# SNES1Chip_SCIC_IGR_D4_Takt_SMD.net
KiCad netlist of a schematic drawn in EAGLE
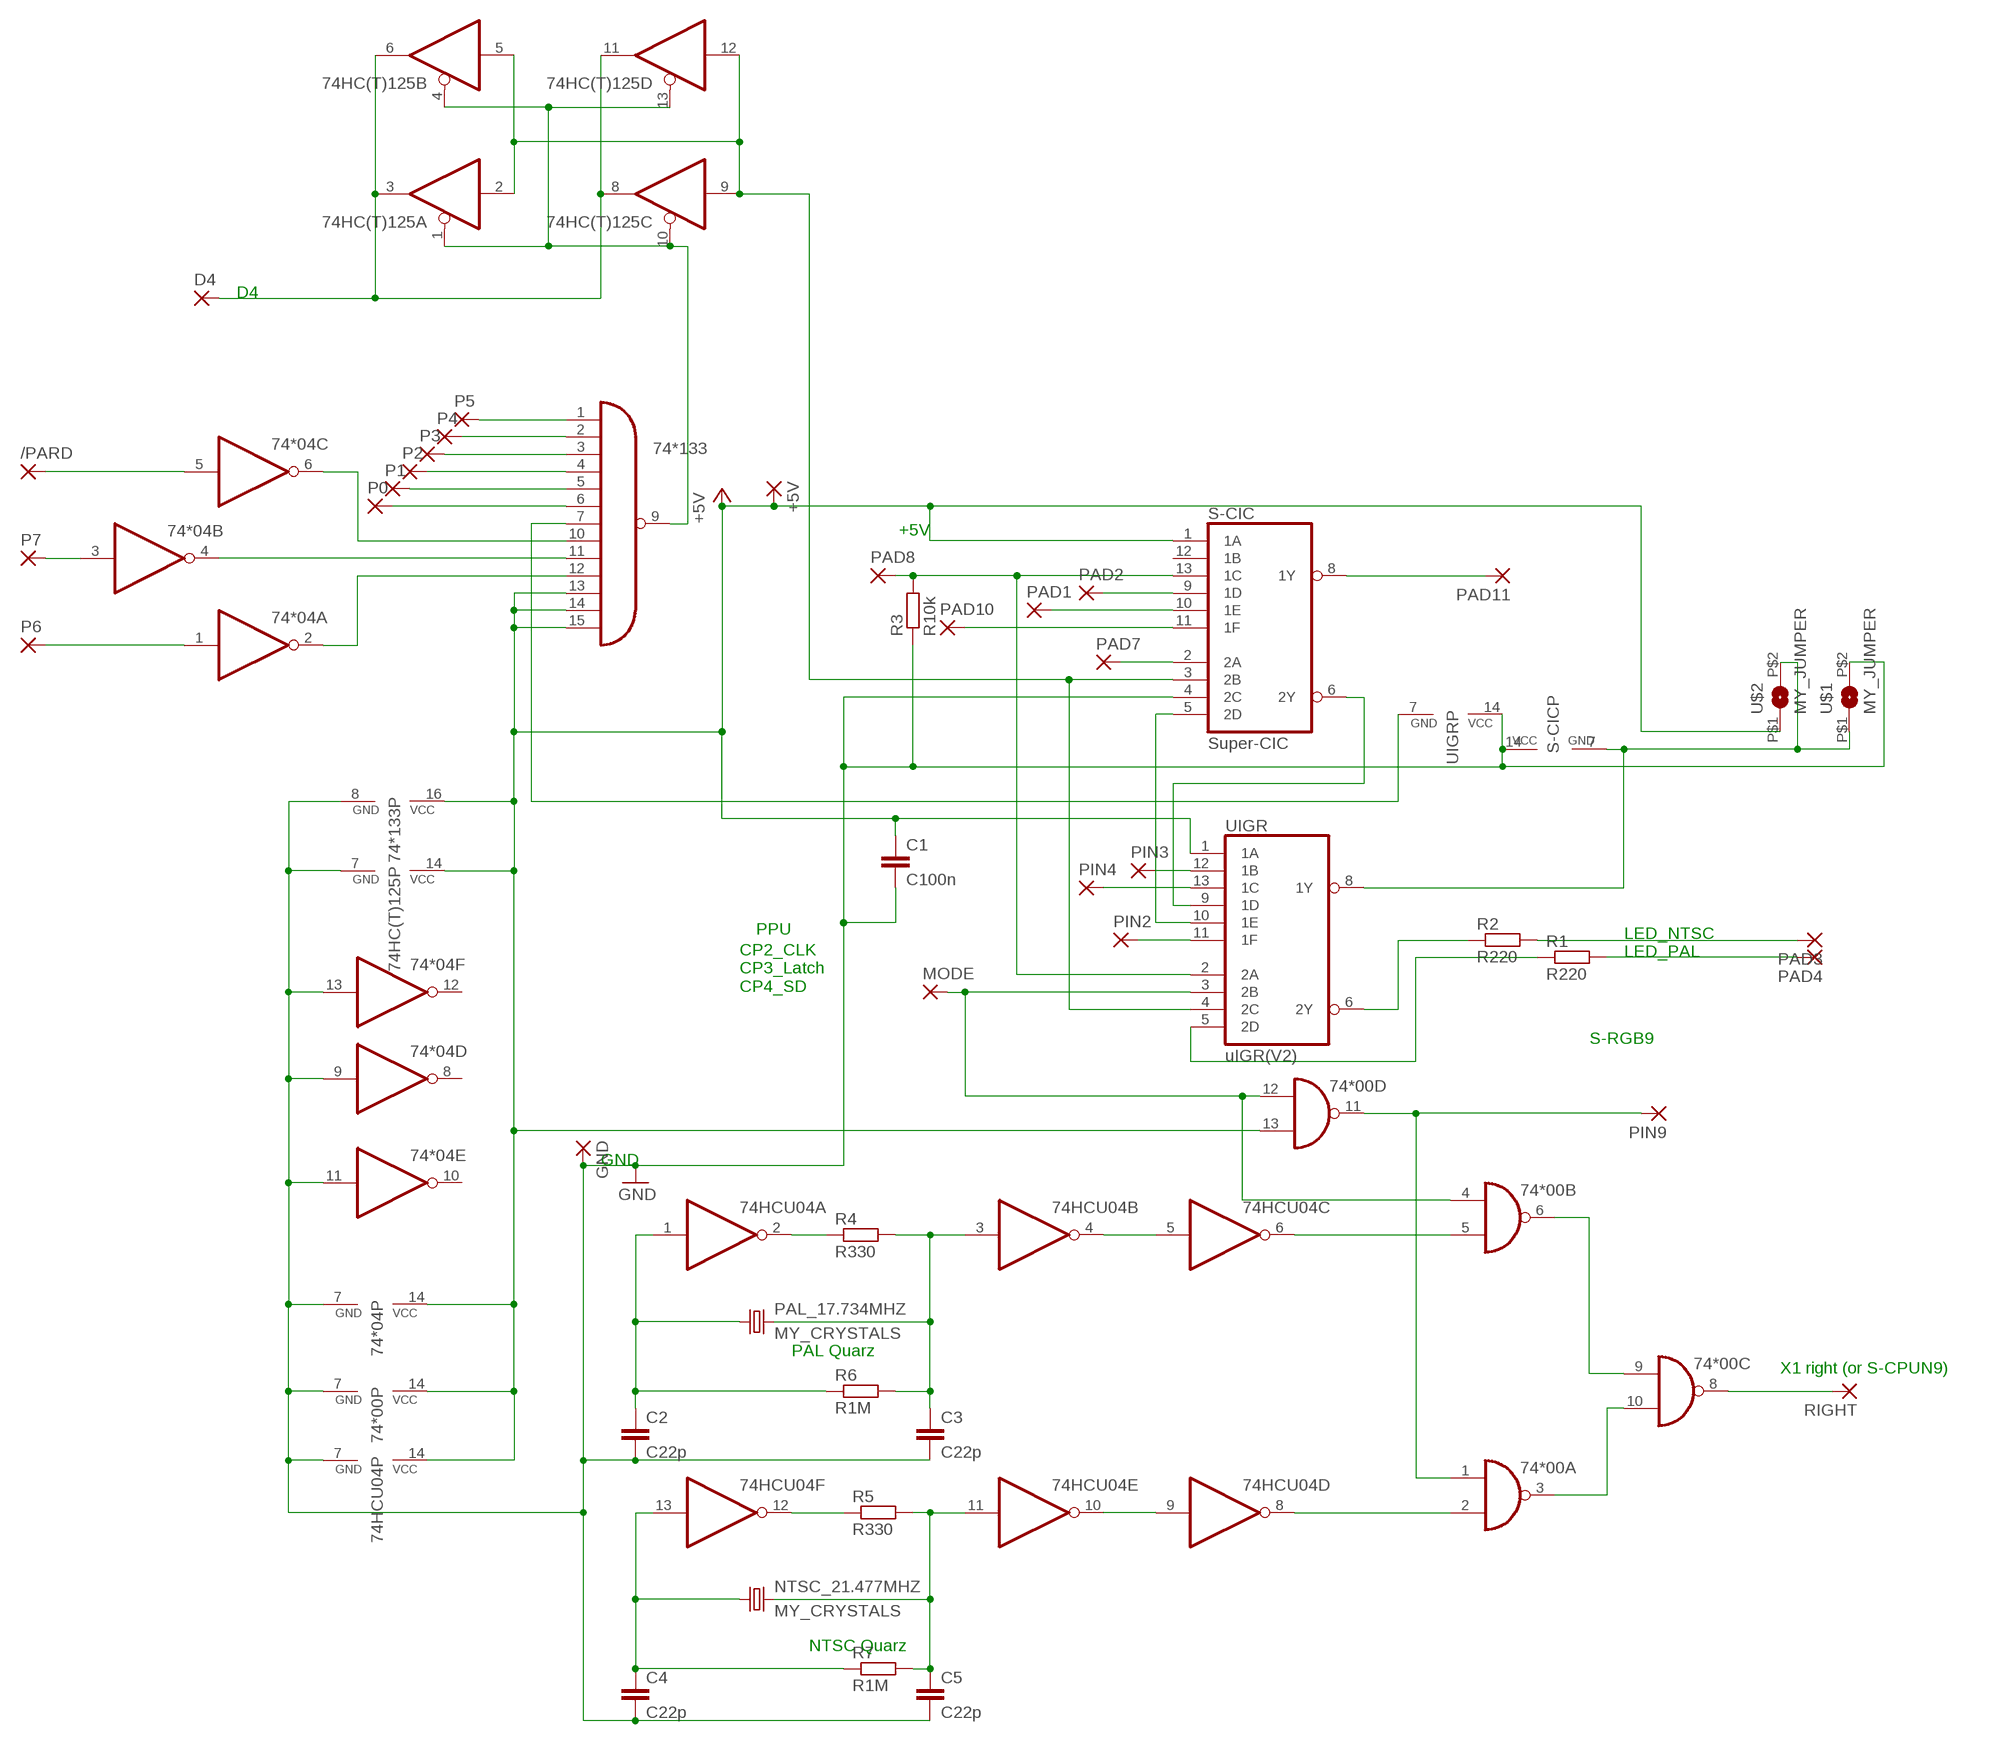
[diagram p0: schematic, sheet 1]

(export (version "E")
  (design (tool "Eeschema 10.0.6"))
  (components
    (comp (ref "+5V")
      (value "SMD2")
      (footprint "eagle-import:SMD1,27-2,54")
      (libsource (lib "eagle-import") (part "SMD2"))
    )
    (comp (ref "/PARD")
      (value "SMD2")
      (footprint "eagle-import:SMD1,27-2,54")
      (libsource (lib "eagle-import") (part "SMD2"))
    )
    (comp (ref "74*00")
      (value "7400D")
      (footprint "eagle-import:SO14")
      (libsource (lib "eagle-import") (part "7400D"))
    )
    (comp (ref "74*04")
      (value "74S04D")
      (footprint "eagle-import:SO14")
      (libsource (lib "eagle-import") (part "7404DS"))
    )
    (comp (ref "74*133")
      (value "74S133D")
      (footprint "eagle-import:SO16")
      (libsource (lib "eagle-import") (part "74133DS"))
    )
    (comp (ref "74HC(T)125")
      (value "74HCT125D")
      (footprint "eagle-import:SO14")
      (libsource (lib "eagle-import") (part "74125DHCT"))
    )
    (comp (ref "74HCU04")
      (value "74HC04D")
      (footprint "eagle-import:SO14")
      (libsource (lib "eagle-import") (part "7404DHC"))
    )
    (comp (ref "C1")
      (value "C100n")
      (footprint "eagle-import:C0805")
      (libsource (lib "eagle-import") (part "C-EUC0805"))
    )
    (comp (ref "C2")
      (value "C22p")
      (footprint "eagle-import:C0805")
      (libsource (lib "eagle-import") (part "C-EUC0805"))
    )
    (comp (ref "C3")
      (value "C22p")
      (footprint "eagle-import:C0805")
      (libsource (lib "eagle-import") (part "C-EUC0805"))
    )
    (comp (ref "C4")
      (value "C22p")
      (footprint "eagle-import:C0805")
      (libsource (lib "eagle-import") (part "C-EUC0805"))
    )
    (comp (ref "C5")
      (value "C22p")
      (footprint "eagle-import:C0805")
      (libsource (lib "eagle-import") (part "C-EUC0805"))
    )
    (comp (ref "D4")
      (value "SMD2")
      (footprint "eagle-import:SMD1,27-2,54")
      (libsource (lib "eagle-import") (part "SMD2"))
    )
    (comp (ref "GND")
      (value "SMD2")
      (footprint "eagle-import:SMD1,27-2,54")
      (libsource (lib "eagle-import") (part "SMD2"))
    )
    (comp (ref "MODE")
      (value "SMD2")
      (footprint "eagle-import:SMD1,27-2,54")
      (libsource (lib "eagle-import") (part "SMD2"))
    )
    (comp (ref "NTSC_21.477MHZ")
      (value "MY_CRYSTALS")
      (footprint "eagle-import:MY_SMD_CRYSTAL2")
      (libsource (lib "eagle-import") (part "MY_CRYSTALS"))
    )
    (comp (ref "P0")
      (value "SMD2")
      (footprint "eagle-import:SMD1,27-2,54")
      (libsource (lib "eagle-import") (part "SMD2"))
    )
    (comp (ref "P1")
      (value "SMD2")
      (footprint "eagle-import:SMD1,27-2,54")
      (libsource (lib "eagle-import") (part "SMD2"))
    )
    (comp (ref "P2")
      (value "SMD2")
      (footprint "eagle-import:SMD1,27-2,54")
      (libsource (lib "eagle-import") (part "SMD2"))
    )
    (comp (ref "P3")
      (value "SMD2")
      (footprint "eagle-import:SMD1,27-2,54")
      (libsource (lib "eagle-import") (part "SMD2"))
    )
    (comp (ref "P4")
      (value "SMD2")
      (footprint "eagle-import:SMD1,27-2,54")
      (libsource (lib "eagle-import") (part "SMD2"))
    )
    (comp (ref "P5")
      (value "SMD2")
      (footprint "eagle-import:SMD1,27-2,54")
      (libsource (lib "eagle-import") (part "SMD2"))
    )
    (comp (ref "P6")
      (value "SMD2")
      (footprint "eagle-import:SMD1,27-2,54")
      (libsource (lib "eagle-import") (part "SMD2"))
    )
    (comp (ref "P7")
      (value "SMD2")
      (footprint "eagle-import:SMD1,27-2,54")
      (libsource (lib "eagle-import") (part "SMD2"))
    )
    (comp (ref "PAD1")
      (value "SMD2")
      (footprint "eagle-import:SMD1,27-2,54")
      (libsource (lib "eagle-import") (part "SMD2"))
    )
    (comp (ref "PAD2")
      (value "SMD2")
      (footprint "eagle-import:SMD1,27-2,54")
      (libsource (lib "eagle-import") (part "SMD2"))
    )
    (comp (ref "PAD3")
      (value "SMD2")
      (footprint "eagle-import:SMD1,27-2,54")
      (libsource (lib "eagle-import") (part "SMD2"))
    )
    (comp (ref "PAD4")
      (value "SMD2")
      (footprint "eagle-import:SMD1,27-2,54")
      (libsource (lib "eagle-import") (part "SMD2"))
    )
    (comp (ref "PAD7")
      (value "SMD2")
      (footprint "eagle-import:SMD1,27-2,54")
      (libsource (lib "eagle-import") (part "SMD2"))
    )
    (comp (ref "PAD8")
      (value "SMD2")
      (footprint "eagle-import:SMD1,27-2,54")
      (libsource (lib "eagle-import") (part "SMD2"))
    )
    (comp (ref "PAD10")
      (value "SMD2")
      (footprint "eagle-import:SMD1,27-2,54")
      (libsource (lib "eagle-import") (part "SMD2"))
    )
    (comp (ref "PAD11")
      (value "SMD2")
      (footprint "eagle-import:SMD1,27-2,54")
      (libsource (lib "eagle-import") (part "SMD2"))
    )
    (comp (ref "PAL_17.734MHZ")
      (value "MY_CRYSTALS")
      (footprint "eagle-import:MY_SMD_CRYSTAL2")
      (libsource (lib "eagle-import") (part "MY_CRYSTALS"))
    )
    (comp (ref "PIN2")
      (value "SMD2")
      (footprint "eagle-import:SMD1,27-2,54")
      (libsource (lib "eagle-import") (part "SMD2"))
    )
    (comp (ref "PIN3")
      (value "SMD2")
      (footprint "eagle-import:SMD1,27-2,54")
      (libsource (lib "eagle-import") (part "SMD2"))
    )
    (comp (ref "PIN4")
      (value "SMD2")
      (footprint "eagle-import:SMD1,27-2,54")
      (libsource (lib "eagle-import") (part "SMD2"))
    )
    (comp (ref "PIN9")
      (value "SMD2")
      (footprint "eagle-import:SMD1,27-2,54")
      (libsource (lib "eagle-import") (part "SMD2"))
    )
    (comp (ref "R1")
      (value "R220")
      (footprint "eagle-import:R0805")
      (libsource (lib "eagle-import") (part "R-EU_R0805"))
    )
    (comp (ref "R2")
      (value "R220")
      (footprint "eagle-import:R0805")
      (libsource (lib "eagle-import") (part "R-EU_R0805"))
    )
    (comp (ref "R3")
      (value "R10k")
      (footprint "eagle-import:R0805")
      (libsource (lib "eagle-import") (part "R-EU_R0805"))
    )
    (comp (ref "R4")
      (value "R330")
      (footprint "eagle-import:R0805")
      (libsource (lib "eagle-import") (part "R-EU_R0805"))
    )
    (comp (ref "R5")
      (value "R330")
      (footprint "eagle-import:R0805")
      (libsource (lib "eagle-import") (part "R-EU_R0805"))
    )
    (comp (ref "R6")
      (value "R1M")
      (footprint "eagle-import:R0805")
      (libsource (lib "eagle-import") (part "R-EU_R0805"))
    )
    (comp (ref "R7")
      (value "R1M")
      (footprint "eagle-import:R0805")
      (libsource (lib "eagle-import") (part "R-EU_R0805"))
    )
    (comp (ref "RIGHT")
      (value "SMD2")
      (footprint "eagle-import:SMD1,27-2,54")
      (libsource (lib "eagle-import") (part "SMD2"))
    )
    (comp (ref "S-CIC")
      (value "Super-CIC")
      (footprint "eagle-import:SO14")
      (libsource (lib "eagle-import") (part "7451DHC"))
    )
    (comp (ref "U$1")
      (value "MY_JUMPER")
      (footprint "eagle-import:MYJUMP")
      (libsource (lib "eagle-import") (part "MY_JUMPER"))
    )
    (comp (ref "U$2")
      (value "MY_JUMPER")
      (footprint "eagle-import:MYJUMP")
      (libsource (lib "eagle-import") (part "MY_JUMPER"))
    )
    (comp (ref "UIGR")
      (value "uIGR(V2)")
      (footprint "eagle-import:SO14")
      (libsource (lib "eagle-import") (part "7451DHC"))
    )
  )
  (nets
    (net (code "1") (name "+5V") (class "Default")
      (node (ref "+5V") (pin "1") (pinfunction "P_1") (pintype "passive"))
      (node (ref "74*00") (pin "13") (pinfunction "I1_13") (pintype "input"))
      (node (ref "74*00") (pin "14") (pinfunction "VCC_14") (pintype "power_in"))
      (node (ref "74*04") (pin "14") (pinfunction "VCC_14") (pintype "power_in"))
      (node (ref "74*133") (pin "13") (pinfunction "I10_13") (pintype "input"))
      (node (ref "74*133") (pin "14") (pinfunction "I11_14") (pintype "input"))
      (node (ref "74*133") (pin "15") (pinfunction "I12_15") (pintype "input"))
      (node (ref "74*133") (pin "16") (pinfunction "VCC_16") (pintype "power_in"))
      (node (ref "74HC(T)125") (pin "14") (pinfunction "VCC_14") (pintype "power_in"))
      (node (ref "74HCU04") (pin "14") (pinfunction "VCC_14") (pintype "power_in"))
      (node (ref "C1") (pin "1") (pinfunction "1_1") (pintype "passive"))
      (node (ref "S-CIC") (pin "1") (pinfunction "1A_1") (pintype "input"))
      (node (ref "U$2") (pin "P$1") (pinfunction "1_P$1") (pintype "passive"))
      (node (ref "UIGR") (pin "1") (pinfunction "1A_1") (pintype "input"))
    )
    (net (code "2") (name "GND") (class "Default")
      (node (ref "74*00") (pin "7") (pinfunction "GND_7") (pintype "power_in"))
      (node (ref "74*04") (pin "11") (pinfunction "I_11") (pintype "input"))
      (node (ref "74*04") (pin "13") (pinfunction "I_13") (pintype "input"))
      (node (ref "74*04") (pin "7") (pinfunction "GND_7") (pintype "power_in"))
      (node (ref "74*04") (pin "9") (pinfunction "I_9") (pintype "input"))
      (node (ref "74*133") (pin "8") (pinfunction "GND_8") (pintype "power_in"))
      (node (ref "74HC(T)125") (pin "7") (pinfunction "GND_7") (pintype "power_in"))
      (node (ref "74HCU04") (pin "7") (pinfunction "GND_7") (pintype "power_in"))
      (node (ref "C1") (pin "2") (pinfunction "2_2") (pintype "passive"))
      (node (ref "C2") (pin "2") (pinfunction "2_2") (pintype "passive"))
      (node (ref "C3") (pin "2") (pinfunction "2_2") (pintype "passive"))
      (node (ref "C4") (pin "2") (pinfunction "2_2") (pintype "passive"))
      (node (ref "C5") (pin "2") (pinfunction "2_2") (pintype "passive"))
      (node (ref "GND") (pin "1") (pinfunction "P_1") (pintype "passive"))
      (node (ref "R3") (pin "1") (pinfunction "1_1") (pintype "passive"))
      (node (ref "S-CIC") (pin "14") (pinfunction "VCC_14") (pintype "power_in"))
      (node (ref "S-CIC") (pin "4") (pinfunction "2C_4") (pintype "input"))
      (node (ref "U$1") (pin "P$2") (pinfunction "2_P$2") (pintype "passive"))
      (node (ref "UIGR") (pin "14") (pinfunction "VCC_14") (pintype "power_in"))
    )
    (net (code "3") (name "Net-(/PARD-P)") (class "Default")
      (node (ref "/PARD") (pin "1") (pinfunction "P_1") (pintype "passive"))
      (node (ref "74*04") (pin "5") (pinfunction "I_5") (pintype "input"))
    )
    (net (code "4") (name "Net-(74*00A-I0)") (class "Default")
      (node (ref "74*00") (pin "1") (pinfunction "I0_1") (pintype "input"))
      (node (ref "74*00") (pin "11") (pinfunction "O_11") (pintype "output"))
      (node (ref "PIN9") (pin "1") (pinfunction "P_1") (pintype "passive"))
    )
    (net (code "5") (name "Net-(74*00A-I1)") (class "Default")
      (node (ref "74*00") (pin "2") (pinfunction "I1_2") (pintype "input"))
      (node (ref "74HCU04") (pin "8") (pinfunction "O_8") (pintype "output"))
    )
    (net (code "6") (name "Net-(74*00A-O)") (class "Default")
      (node (ref "74*00") (pin "10") (pinfunction "I1_10") (pintype "input"))
      (node (ref "74*00") (pin "3") (pinfunction "O_3") (pintype "output"))
    )
    (net (code "7") (name "Net-(74*00B-I0)") (class "Default")
      (node (ref "74*00") (pin "12") (pinfunction "I0_12") (pintype "input"))
      (node (ref "74*00") (pin "4") (pinfunction "I0_4") (pintype "input"))
      (node (ref "MODE") (pin "1") (pinfunction "P_1") (pintype "passive"))
      (node (ref "UIGR") (pin "3") (pinfunction "2B_3") (pintype "input"))
    )
    (net (code "8") (name "Net-(74*00B-I1)") (class "Default")
      (node (ref "74*00") (pin "5") (pinfunction "I1_5") (pintype "input"))
      (node (ref "74HCU04") (pin "6") (pinfunction "O_6") (pintype "output"))
    )
    (net (code "9") (name "Net-(74*00B-O)") (class "Default")
      (node (ref "74*00") (pin "6") (pinfunction "O_6") (pintype "output"))
      (node (ref "74*00") (pin "9") (pinfunction "I0_9") (pintype "input"))
    )
    (net (code "10") (name "Net-(74*00C-O)") (class "Default")
      (node (ref "74*00") (pin "8") (pinfunction "O_8") (pintype "output"))
      (node (ref "RIGHT") (pin "1") (pinfunction "P_1") (pintype "passive"))
    )
    (net (code "11") (name "Net-(74*04A-I)") (class "Default")
      (node (ref "74*04") (pin "1") (pinfunction "I_1") (pintype "input"))
      (node (ref "P6") (pin "1") (pinfunction "P_1") (pintype "passive"))
    )
    (net (code "12") (name "Net-(74*04A-O)") (class "Default")
      (node (ref "74*04") (pin "2") (pinfunction "O_2") (pintype "output"))
      (node (ref "74*133") (pin "12") (pinfunction "I9_12") (pintype "input"))
    )
    (net (code "13") (name "Net-(74*04B-I)") (class "Default")
      (node (ref "74*04") (pin "3") (pinfunction "I_3") (pintype "input"))
      (node (ref "P7") (pin "1") (pinfunction "P_1") (pintype "passive"))
    )
    (net (code "14") (name "Net-(74*04B-O)") (class "Default")
      (node (ref "74*04") (pin "4") (pinfunction "O_4") (pintype "output"))
      (node (ref "74*133") (pin "11") (pinfunction "I8_11") (pintype "input"))
    )
    (net (code "15") (name "Net-(74*04C-O)") (class "Default")
      (node (ref "74*04") (pin "6") (pinfunction "O_6") (pintype "output"))
      (node (ref "74*133") (pin "10") (pinfunction "I7_10") (pintype "input"))
    )
    (net (code "16") (name "Net-(74*133A-I0)") (class "Default")
      (node (ref "74*133") (pin "1") (pinfunction "I0_1") (pintype "input"))
      (node (ref "P5") (pin "1") (pinfunction "P_1") (pintype "passive"))
    )
    (net (code "17") (name "Net-(74*133A-I1)") (class "Default")
      (node (ref "74*133") (pin "2") (pinfunction "I1_2") (pintype "input"))
      (node (ref "P4") (pin "1") (pinfunction "P_1") (pintype "passive"))
    )
    (net (code "18") (name "Net-(74*133A-I2)") (class "Default")
      (node (ref "74*133") (pin "3") (pinfunction "I2_3") (pintype "input"))
      (node (ref "P3") (pin "1") (pinfunction "P_1") (pintype "passive"))
    )
    (net (code "19") (name "Net-(74*133A-I3)") (class "Default")
      (node (ref "74*133") (pin "4") (pinfunction "I3_4") (pintype "input"))
      (node (ref "P2") (pin "1") (pinfunction "P_1") (pintype "passive"))
    )
    (net (code "20") (name "Net-(74*133A-I4)") (class "Default")
      (node (ref "74*133") (pin "5") (pinfunction "I4_5") (pintype "input"))
      (node (ref "P1") (pin "1") (pinfunction "P_1") (pintype "passive"))
    )
    (net (code "21") (name "Net-(74*133A-I5)") (class "Default")
      (node (ref "74*133") (pin "6") (pinfunction "I5_6") (pintype "input"))
      (node (ref "P0") (pin "1") (pinfunction "P_1") (pintype "passive"))
    )
    (net (code "22") (name "Net-(74*133A-I6)") (class "Default")
      (node (ref "74*133") (pin "7") (pinfunction "I6_7") (pintype "input"))
      (node (ref "UIGR") (pin "7") (pinfunction "GND_7") (pintype "power_in"))
    )
    (net (code "23") (name "Net-(74*133A-O)") (class "Default")
      (node (ref "74*133") (pin "9") (pinfunction "O_9") (pintype "output"))
      (node (ref "74HC(T)125") (pin "1") (pinfunction "OE_1") (pintype "input"))
      (node (ref "74HC(T)125") (pin "10") (pinfunction "OE_10") (pintype "input"))
      (node (ref "74HC(T)125") (pin "13") (pinfunction "OE_13") (pintype "input"))
      (node (ref "74HC(T)125") (pin "4") (pinfunction "OE_4") (pintype "input"))
    )
    (net (code "24") (name "Net-(74HC(T)125A-I)") (class "Default")
      (node (ref "74HC(T)125") (pin "12") (pinfunction "I_12") (pintype "input"))
      (node (ref "74HC(T)125") (pin "2") (pinfunction "I_2") (pintype "input"))
      (node (ref "74HC(T)125") (pin "5") (pinfunction "I_5") (pintype "input"))
      (node (ref "74HC(T)125") (pin "9") (pinfunction "I_9") (pintype "input"))
      (node (ref "S-CIC") (pin "3") (pinfunction "2B_3") (pintype "input"))
      (node (ref "UIGR") (pin "4") (pinfunction "2C_4") (pintype "input"))
    )
    (net (code "25") (name "Net-(74HC(T)125A-O)") (class "Default")
      (node (ref "74HC(T)125") (pin "11") (pinfunction "O_11") (pintype "tri_state"))
      (node (ref "74HC(T)125") (pin "3") (pinfunction "O_3") (pintype "tri_state"))
      (node (ref "74HC(T)125") (pin "6") (pinfunction "O_6") (pintype "tri_state"))
      (node (ref "74HC(T)125") (pin "8") (pinfunction "O_8") (pintype "tri_state"))
      (node (ref "D4") (pin "1") (pinfunction "P_1") (pintype "passive"))
    )
    (net (code "26") (name "Net-(74HCU04A-I)") (class "Default")
      (node (ref "74HCU04") (pin "1") (pinfunction "I_1") (pintype "input"))
      (node (ref "C2") (pin "1") (pinfunction "1_1") (pintype "passive"))
      (node (ref "PAL_17.734MHZ") (pin "1") (pinfunction "1_1") (pintype "passive"))
      (node (ref "R6") (pin "1") (pinfunction "1_1") (pintype "passive"))
    )
    (net (code "27") (name "Net-(74HCU04A-O)") (class "Default")
      (node (ref "74HCU04") (pin "2") (pinfunction "O_2") (pintype "output"))
      (node (ref "R4") (pin "1") (pinfunction "1_1") (pintype "passive"))
    )
    (net (code "28") (name "Net-(74HCU04B-I)") (class "Default")
      (node (ref "74HCU04") (pin "3") (pinfunction "I_3") (pintype "input"))
      (node (ref "C3") (pin "1") (pinfunction "1_1") (pintype "passive"))
      (node (ref "PAL_17.734MHZ") (pin "2") (pinfunction "2_2") (pintype "passive"))
      (node (ref "R4") (pin "2") (pinfunction "2_2") (pintype "passive"))
      (node (ref "R6") (pin "2") (pinfunction "2_2") (pintype "passive"))
    )
    (net (code "29") (name "Net-(74HCU04B-O)") (class "Default")
      (node (ref "74HCU04") (pin "4") (pinfunction "O_4") (pintype "output"))
      (node (ref "74HCU04") (pin "5") (pinfunction "I_5") (pintype "input"))
    )
    (net (code "30") (name "Net-(74HCU04D-I)") (class "Default")
      (node (ref "74HCU04") (pin "10") (pinfunction "O_10") (pintype "output"))
      (node (ref "74HCU04") (pin "9") (pinfunction "I_9") (pintype "input"))
    )
    (net (code "31") (name "Net-(74HCU04E-I)") (class "Default")
      (node (ref "74HCU04") (pin "11") (pinfunction "I_11") (pintype "input"))
      (node (ref "C5") (pin "1") (pinfunction "1_1") (pintype "passive"))
      (node (ref "NTSC_21.477MHZ") (pin "2") (pinfunction "2_2") (pintype "passive"))
      (node (ref "R5") (pin "2") (pinfunction "2_2") (pintype "passive"))
      (node (ref "R7") (pin "2") (pinfunction "2_2") (pintype "passive"))
    )
    (net (code "32") (name "Net-(74HCU04F-I)") (class "Default")
      (node (ref "74HCU04") (pin "13") (pinfunction "I_13") (pintype "input"))
      (node (ref "C4") (pin "1") (pinfunction "1_1") (pintype "passive"))
      (node (ref "NTSC_21.477MHZ") (pin "1") (pinfunction "1_1") (pintype "passive"))
      (node (ref "R7") (pin "1") (pinfunction "1_1") (pintype "passive"))
    )
    (net (code "33") (name "Net-(74HCU04F-O)") (class "Default")
      (node (ref "74HCU04") (pin "12") (pinfunction "O_12") (pintype "output"))
      (node (ref "R5") (pin "1") (pinfunction "1_1") (pintype "passive"))
    )
    (net (code "34") (name "Net-(PAD1-P)") (class "Default")
      (node (ref "PAD1") (pin "1") (pinfunction "P_1") (pintype "passive"))
      (node (ref "S-CIC") (pin "10") (pinfunction "1E_10") (pintype "input"))
    )
    (net (code "35") (name "Net-(PAD2-P)") (class "Default")
      (node (ref "PAD2") (pin "1") (pinfunction "P_1") (pintype "passive"))
      (node (ref "S-CIC") (pin "9") (pinfunction "1D_9") (pintype "input"))
    )
    (net (code "36") (name "Net-(PAD3-P)") (class "Default")
      (node (ref "PAD3") (pin "1") (pinfunction "P_1") (pintype "passive"))
      (node (ref "R2") (pin "2") (pinfunction "2_2") (pintype "passive"))
    )
    (net (code "37") (name "Net-(PAD4-P)") (class "Default")
      (node (ref "PAD4") (pin "1") (pinfunction "P_1") (pintype "passive"))
      (node (ref "R1") (pin "2") (pinfunction "2_2") (pintype "passive"))
    )
    (net (code "38") (name "Net-(PAD7-P)") (class "Default")
      (node (ref "PAD7") (pin "1") (pinfunction "P_1") (pintype "passive"))
      (node (ref "S-CIC") (pin "2") (pinfunction "2A_2") (pintype "input"))
    )
    (net (code "39") (name "Net-(PAD8-P)") (class "Default")
      (node (ref "PAD8") (pin "1") (pinfunction "P_1") (pintype "passive"))
      (node (ref "R3") (pin "2") (pinfunction "2_2") (pintype "passive"))
      (node (ref "S-CIC") (pin "13") (pinfunction "1C_13") (pintype "input"))
      (node (ref "UIGR") (pin "2") (pinfunction "2A_2") (pintype "input"))
    )
    (net (code "40") (name "Net-(PAD10-P)") (class "Default")
      (node (ref "PAD10") (pin "1") (pinfunction "P_1") (pintype "passive"))
      (node (ref "S-CIC") (pin "11") (pinfunction "1F_11") (pintype "input"))
    )
    (net (code "41") (name "Net-(PAD11-P)") (class "Default")
      (node (ref "PAD11") (pin "1") (pinfunction "P_1") (pintype "passive"))
      (node (ref "S-CIC") (pin "8") (pinfunction "1Y_8") (pintype "output"))
    )
    (net (code "42") (name "Net-(PIN2-P)") (class "Default")
      (node (ref "PIN2") (pin "1") (pinfunction "P_1") (pintype "passive"))
      (node (ref "UIGR") (pin "11") (pinfunction "1F_11") (pintype "input"))
    )
    (net (code "43") (name "Net-(PIN3-P)") (class "Default")
      (node (ref "PIN3") (pin "1") (pinfunction "P_1") (pintype "passive"))
      (node (ref "UIGR") (pin "12") (pinfunction "1B_12") (pintype "input"))
    )
    (net (code "44") (name "Net-(PIN4-P)") (class "Default")
      (node (ref "PIN4") (pin "1") (pinfunction "P_1") (pintype "passive"))
      (node (ref "UIGR") (pin "13") (pinfunction "1C_13") (pintype "input"))
    )
    (net (code "45") (name "Net-(S-CICA-2D)") (class "Default")
      (node (ref "S-CIC") (pin "5") (pinfunction "2D_5") (pintype "input"))
      (node (ref "UIGR") (pin "10") (pinfunction "1E_10") (pintype "input"))
    )
    (net (code "46") (name "Net-(S-CICA-2Y)") (class "Default")
      (node (ref "S-CIC") (pin "6") (pinfunction "2Y_6") (pintype "output"))
      (node (ref "UIGR") (pin "9") (pinfunction "1D_9") (pintype "input"))
    )
    (net (code "47") (name "Net-(S-CICB-GND)") (class "Default")
      (node (ref "S-CIC") (pin "7") (pinfunction "GND_7") (pintype "power_in"))
      (node (ref "U$1") (pin "P$1") (pinfunction "1_P$1") (pintype "passive"))
      (node (ref "U$2") (pin "P$2") (pinfunction "2_P$2") (pintype "passive"))
      (node (ref "UIGR") (pin "8") (pinfunction "1Y_8") (pintype "output"))
    )
    (net (code "48") (name "Net-(UIGRA-2D)") (class "Default")
      (node (ref "R1") (pin "1") (pinfunction "1_1") (pintype "passive"))
      (node (ref "UIGR") (pin "5") (pinfunction "2D_5") (pintype "input"))
    )
    (net (code "49") (name "Net-(UIGRA-2Y)") (class "Default")
      (node (ref "R2") (pin "1") (pinfunction "1_1") (pintype "passive"))
      (node (ref "UIGR") (pin "6") (pinfunction "2Y_6") (pintype "output"))
    )
    (net (code "50") (name "unconnected-(74*04D-O-Pad8)") (class "Default")
      (node (ref "74*04") (pin "8") (pinfunction "O_8") (pintype "output"))
    )
    (net (code "51") (name "unconnected-(74*04E-O-Pad10)") (class "Default")
      (node (ref "74*04") (pin "10") (pinfunction "O_10") (pintype "output"))
    )
    (net (code "52") (name "unconnected-(74*04F-O-Pad12)") (class "Default")
      (node (ref "74*04") (pin "12") (pinfunction "O_12") (pintype "output"))
    )
    (net (code "53") (name "unconnected-(S-CICA-1B-Pad12)") (class "Default")
      (node (ref "S-CIC") (pin "12") (pinfunction "1B_12") (pintype "input"))
    )
  )
)
